# Motors_and_Servos.net
KiCad netlist of a schematic drawn in Altium Designer
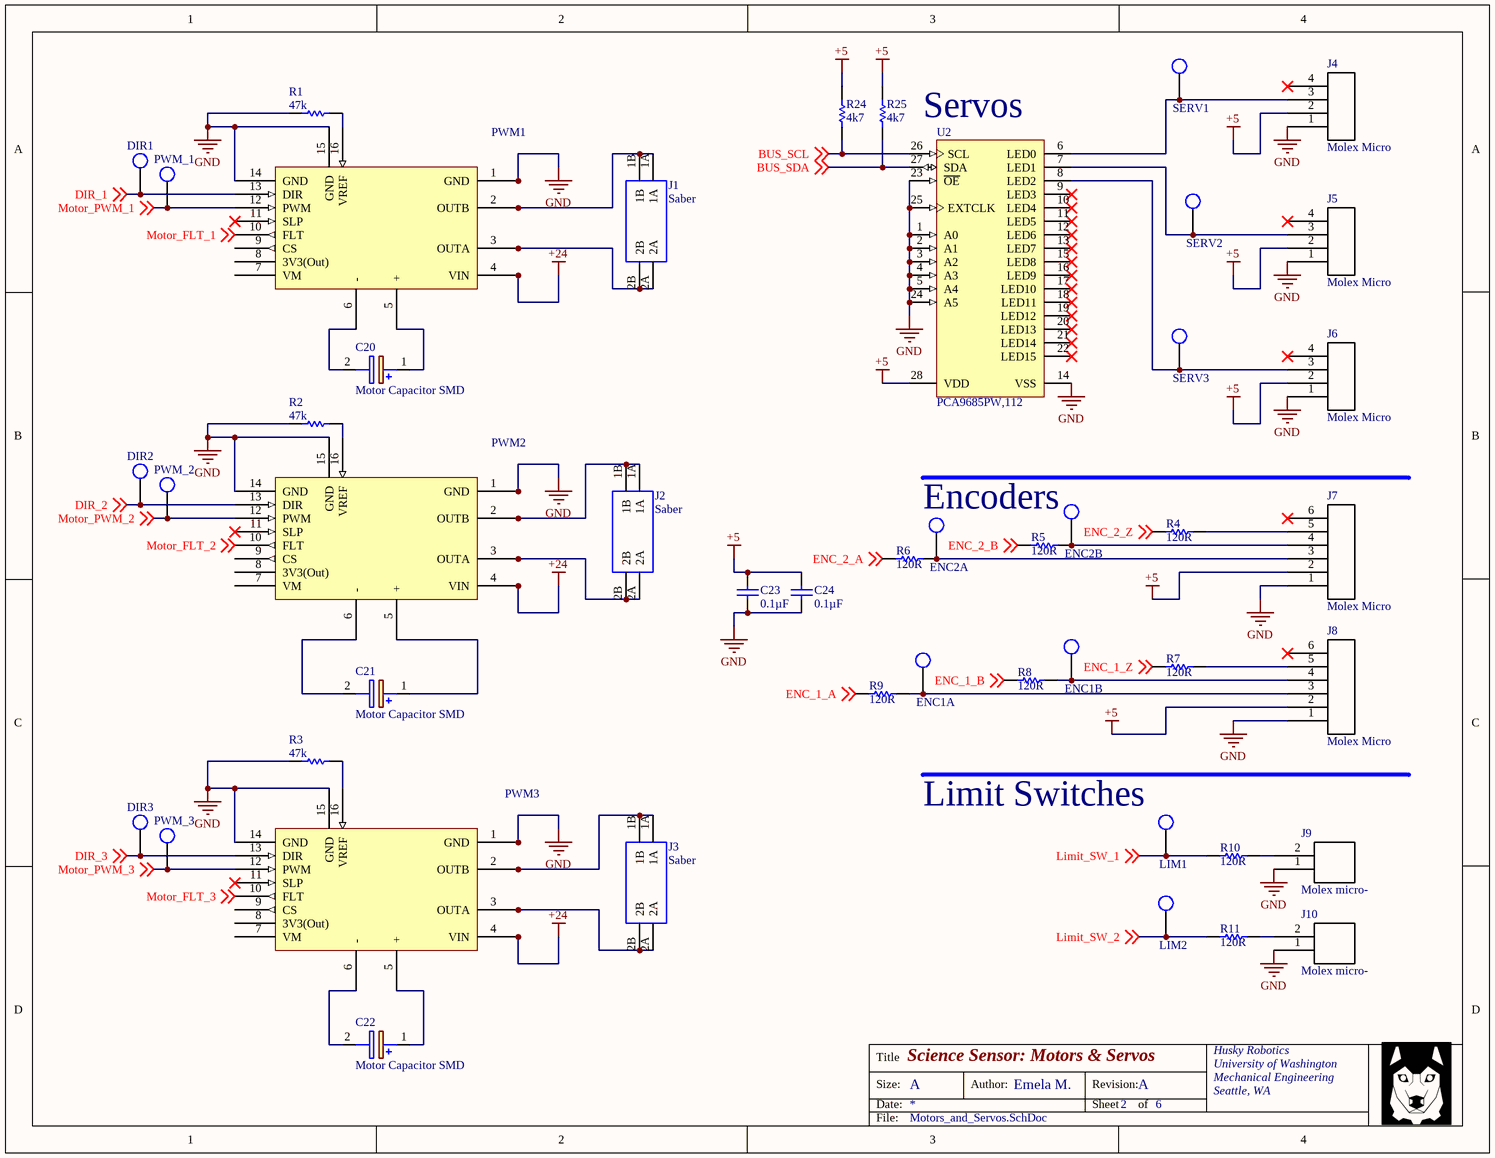
[diagram p0: Motors_and_Servos.SchDoc]

(export (version "E")
  (design (tool "Eeschema 10.0.6"))
  (components
    (comp (ref "C20")
      (value "Motor Capacitor SMD")
      (footprint "CAP_SMD_CAN")
      (description "Capacitor Polarised")
      (fields
        (field (name "MANUFACTURER_PART_NUMBER") "EEE-FK1V331AP")
        (field (name "MOUSER PART NUMBER") "667-EEE-FK1V331AP")
      )
      (libsource (lib "Husky Robotics Standard Library 2019-2020") (part "Motor Capacitor SMD"))
    )
    (comp (ref "C21")
      (value "Motor Capacitor SMD")
      (footprint "CAP_SMD_CAN")
      (description "Capacitor Polarised")
      (fields
        (field (name "MANUFACTURER_PART_NUMBER") "EEE-FK1V331AP")
        (field (name "MOUSER PART NUMBER") "667-EEE-FK1V331AP")
      )
      (libsource (lib "Husky Robotics Standard Library 2019-2020") (part "Motor Capacitor SMD"))
    )
    (comp (ref "C22")
      (value "Motor Capacitor SMD")
      (footprint "CAP_SMD_CAN")
      (description "Capacitor Polarised")
      (fields
        (field (name "MANUFACTURER_PART_NUMBER") "EEE-FK1V331AP")
        (field (name "MOUSER PART NUMBER") "667-EEE-FK1V331AP")
      )
      (libsource (lib "Husky Robotics Standard Library 2019-2020") (part "Motor Capacitor SMD"))
    )
    (comp (ref "C23")
      (value "Capacitor 0805")
      (footprint "Cap 0805")
      (description "Standard Capacitor")
      (fields (field (name "MANUFACTURER") "AVX") (field (name "CAPACITANCE") "0.1µF"))
      (libsource (lib "Standard Cap") (part "Capacitor 0805"))
    )
    (comp (ref "C24")
      (value "Capacitor 0805")
      (footprint "Cap 0805")
      (description "Standard Capacitor")
      (fields (field (name "MANUFACTURER") "AVX") (field (name "CAPACITANCE") "0.1µF"))
      (libsource (lib "Standard Cap") (part "Capacitor 0805"))
    )
    (comp (ref "DIR1")
      (value "Test Point")
      (footprint "Test Point Through-hole")
      (libsource (lib "Husky Robotics Standard Library 2019-2020") (part "Test Point"))
    )
    (comp (ref "DIR2")
      (value "Test Point")
      (footprint "Test Point Through-hole")
      (libsource (lib "Husky Robotics Standard Library 2019-2020") (part "Test Point"))
    )
    (comp (ref "DIR3")
      (value "Test Point")
      (footprint "Test Point Through-hole")
      (libsource (lib "Husky Robotics Standard Library 2019-2020") (part "Test Point"))
    )
    (comp (ref "ENC1A")
      (value "Test Point")
      (footprint "Test Point Through-hole")
      (libsource (lib "Husky Robotics Standard Library 2019-2020") (part "Test Point"))
    )
    (comp (ref "ENC1B")
      (value "Test Point")
      (footprint "Test Point Through-hole")
      (libsource (lib "Husky Robotics Standard Library 2019-2020") (part "Test Point"))
    )
    (comp (ref "ENC2A")
      (value "Test Point")
      (footprint "Test Point Through-hole")
      (libsource (lib "Husky Robotics Standard Library 2019-2020") (part "Test Point"))
    )
    (comp (ref "ENC2B")
      (value "Test Point")
      (footprint "Test Point Through-hole")
      (libsource (lib "Husky Robotics Standard Library 2019-2020") (part "Test Point"))
    )
    (comp (ref "J1")
      (value "Saber")
      (footprint "SABER R/A")
      (libsource (lib "Husky Robotics Standard Library 2019-2020") (part "Saber"))
    )
    (comp (ref "J2")
      (value "Saber")
      (footprint "SABER R/A")
      (libsource (lib "Husky Robotics Standard Library 2019-2020") (part "Saber"))
    )
    (comp (ref "J3")
      (value "Saber")
      (footprint "SABER R/A")
      (libsource (lib "Husky Robotics Standard Library 2019-2020") (part "Saber"))
    )
    (comp (ref "J4")
      (value "Molex Micro")
      (footprint "MICROFIT R/A 4 PIN")
      (description "Molex micro-fit 3.0 dual row header. P/N 0430450427")
      (libsource (lib "Husky Robotics Standard Library 2019-2020") (part "Molex micro-fit 4-pin (Single row schematic)"))
    )
    (comp (ref "J5")
      (value "Molex Micro")
      (footprint "MICROFIT R/A 4 PIN")
      (description "Molex micro-fit 3.0 dual row header. P/N 0430450427")
      (libsource (lib "Husky Robotics Standard Library 2019-2020") (part "Molex micro-fit 4-pin (Single row schematic)"))
    )
    (comp (ref "J6")
      (value "Molex Micro")
      (footprint "MICROFIT R/A 4 PIN")
      (description "Molex micro-fit 3.0 dual row header. P/N 0430450427")
      (libsource (lib "Husky Robotics Standard Library 2019-2020") (part "Molex micro-fit 4-pin (Single row schematic)"))
    )
    (comp (ref "J7")
      (value "Molex Micro")
      (footprint "MICROFIT R/A 6 PIN")
      (description "Molex micro-fit 3.0 dual row connector. P/N 0430450627")
      (libsource (lib "Husky Robotics Standard Library 2019-2020") (part "Molex micro-fit 6-pin (single row schematic)"))
    )
    (comp (ref "J8")
      (value "Molex Micro")
      (footprint "MICROFIT R/A 6 PIN")
      (description "Molex micro-fit 3.0 dual row connector. P/N 0430450627")
      (libsource (lib "Husky Robotics Standard Library 2019-2020") (part "Molex micro-fit 6-pin (single row schematic)"))
    )
    (comp (ref "J9")
      (value "Molex micro-")
      (footprint "microfit R/A 2 pin")
      (description "Molex micro-fit 3.0. Molex P/N 0430450227")
      (libsource (lib "Husky Robotics Standard Library 2019-2020") (part "Molex micro-fit 2-pin"))
    )
    (comp (ref "J10")
      (value "Molex micro-")
      (footprint "microfit R/A 2 pin")
      (description "Molex micro-fit 3.0. Molex P/N 0430450227")
      (libsource (lib "Husky Robotics Standard Library 2019-2020") (part "Molex micro-fit 2-pin"))
    )
    (comp (ref "LIM1")
      (value "Test Point")
      (footprint "Test Point Through-hole")
      (libsource (lib "Husky Robotics Standard Library 2019-2020") (part "Test Point"))
    )
    (comp (ref "LIM2")
      (value "Test Point")
      (footprint "Test Point Through-hole")
      (libsource (lib "Husky Robotics Standard Library 2019-2020") (part "Test Point"))
    )
    (comp (ref "PWM1")
      (value "6.5V - 40V")
      (footprint "Pololu_G2_Driver_24v21")
      (libsource (lib "Husky Robotics Standard Library 2019-2020") (part "Pololu G2 High-Power Motor Driver 24v21"))
    )
    (comp (ref "PWM2")
      (value "6.5V - 40V")
      (footprint "Pololu_G2_Driver_24v21")
      (libsource (lib "Husky Robotics Standard Library 2019-2020") (part "Pololu G2 High-Power Motor Driver 24v21"))
    )
    (comp (ref "PWM3")
      (value "6.5V - 40V")
      (footprint "Pololu_G2_Driver_24v21")
      (libsource (lib "Husky Robotics Standard Library 2019-2020") (part "Pololu G2 High-Power Motor Driver 24v21"))
    )
    (comp (ref "PWM_1")
      (value "Test Point")
      (footprint "Test Point Through-hole")
      (libsource (lib "Husky Robotics Standard Library 2019-2020") (part "Test Point"))
    )
    (comp (ref "PWM_2")
      (value "Test Point")
      (footprint "Test Point Through-hole")
      (libsource (lib "Husky Robotics Standard Library 2019-2020") (part "Test Point"))
    )
    (comp (ref "PWM_3")
      (value "Test Point")
      (footprint "Test Point Through-hole")
      (libsource (lib "Husky Robotics Standard Library 2019-2020") (part "Test Point"))
    )
    (comp (ref "R1")
      (value "47k")
      (footprint "RESC0805(2012)_N")
      (description "Generic 0805 Resistor")
      (fields (field (name "TOLERANCE") "5 %") (field (name "POWER") "0.125 W"))
      (libsource (lib "Husky Robotics Standard Library 2019-2020") (part "Resistor 0805"))
    )
    (comp (ref "R2")
      (value "47k")
      (footprint "RESC0805(2012)_N")
      (description "Generic 0805 Resistor")
      (fields (field (name "TOLERANCE") "5 %") (field (name "POWER") "0.125 W"))
      (libsource (lib "Husky Robotics Standard Library 2019-2020") (part "Resistor 0805"))
    )
    (comp (ref "R3")
      (value "47k")
      (footprint "RESC0805(2012)_N")
      (description "Generic 0805 Resistor")
      (fields (field (name "TOLERANCE") "5 %") (field (name "POWER") "0.125 W"))
      (libsource (lib "Husky Robotics Standard Library 2019-2020") (part "Resistor 0805"))
    )
    (comp (ref "R4")
      (value "120R")
      (footprint "RESC0805(2012)_N")
      (description "Generic 0805 Resistor")
      (fields (field (name "TOLERANCE") "5 %") (field (name "POWER") "0.125 W"))
      (libsource (lib "Husky Robotics Standard Library 2019-2020") (part "Resistor 0805"))
    )
    (comp (ref "R5")
      (value "120R")
      (footprint "RESC0805(2012)_N")
      (description "Generic 0805 Resistor")
      (fields (field (name "TOLERANCE") "5 %") (field (name "POWER") "0.125 W"))
      (libsource (lib "Husky Robotics Standard Library 2019-2020") (part "Resistor 0805"))
    )
    (comp (ref "R6")
      (value "120R")
      (footprint "RESC0805(2012)_N")
      (description "Generic 0805 Resistor")
      (fields (field (name "TOLERANCE") "5 %") (field (name "POWER") "0.125 W"))
      (libsource (lib "Husky Robotics Standard Library 2019-2020") (part "Resistor 0805"))
    )
    (comp (ref "R7")
      (value "120R")
      (footprint "RESC0805(2012)_N")
      (description "Generic 0805 Resistor")
      (fields (field (name "TOLERANCE") "5 %") (field (name "POWER") "0.125 W"))
      (libsource (lib "Husky Robotics Standard Library 2019-2020") (part "Resistor 0805"))
    )
    (comp (ref "R8")
      (value "120R")
      (footprint "RESC0805(2012)_N")
      (description "Generic 0805 Resistor")
      (fields (field (name "TOLERANCE") "5 %") (field (name "POWER") "0.125 W"))
      (libsource (lib "Husky Robotics Standard Library 2019-2020") (part "Resistor 0805"))
    )
    (comp (ref "R9")
      (value "120R")
      (footprint "RESC0805(2012)_N")
      (description "Generic 0805 Resistor")
      (fields (field (name "TOLERANCE") "5 %") (field (name "POWER") "0.125 W"))
      (libsource (lib "Husky Robotics Standard Library 2019-2020") (part "Resistor 0805"))
    )
    (comp (ref "R10")
      (value "120R")
      (footprint "RESC0805(2012)_N")
      (description "Generic 0805 Resistor")
      (fields (field (name "TOLERANCE") "5 %") (field (name "POWER") "0.125 W"))
      (libsource (lib "Husky Robotics Standard Library 2019-2020") (part "Resistor 0805"))
    )
    (comp (ref "R11")
      (value "120R")
      (footprint "RESC0805(2012)_N")
      (description "Generic 0805 Resistor")
      (fields (field (name "TOLERANCE") "5 %") (field (name "POWER") "0.125 W"))
      (libsource (lib "Husky Robotics Standard Library 2019-2020") (part "Resistor 0805"))
    )
    (comp (ref "R24")
      (value "4k7")
      (footprint "RESC0805(2012)_N")
      (description "Generic 0805 Resistor")
      (fields (field (name "TOLERANCE") "5 %") (field (name "POWER") "0.125 W"))
      (libsource (lib "Husky Robotics Standard Library 2019-2020") (part "Resistor 0805"))
    )
    (comp (ref "R25")
      (value "4k7")
      (footprint "RESC0805(2012)_N")
      (description "Generic 0805 Resistor")
      (fields (field (name "TOLERANCE") "5 %") (field (name "POWER") "0.125 W"))
      (libsource (lib "Husky Robotics Standard Library 2019-2020") (part "Resistor 0805"))
    )
    (comp (ref "SERV1")
      (value "Test Point")
      (footprint "Test Point Through-hole")
      (libsource (lib "Husky Robotics Standard Library 2019-2020") (part "Test Point"))
    )
    (comp (ref "SERV2")
      (value "Test Point")
      (footprint "Test Point Through-hole")
      (libsource (lib "Husky Robotics Standard Library 2019-2020") (part "Test Point"))
    )
    (comp (ref "SERV3")
      (value "Test Point")
      (footprint "Test Point Through-hole")
      (libsource (lib "Husky Robotics Standard Library 2019-2020") (part "Test Point"))
    )
    (comp (ref "U2")
      (value "PCA9685PW,112")
      (footprint "SOT361-1_V")
      (fields (field (name "PARTNUMBER") "PCA9685"))
      (libsource (lib "Altium Content Vault") (part "NXP-PCA9685-SOT361-1"))
    )
  )
  (nets
    (net (code "1") (name "+5") (class "Default")
      (node (ref "C23") (pin "2") (pinfunction "2_2") (pintype "passive"))
      (node (ref "C24") (pin "2") (pinfunction "2_2") (pintype "passive"))
      (node (ref "J4") (pin "2") (pintype "passive"))
      (node (ref "J5") (pin "2") (pintype "passive"))
      (node (ref "J6") (pin "2") (pintype "passive"))
      (node (ref "J7") (pin "2") (pintype "passive"))
      (node (ref "J8") (pin "2") (pintype "passive"))
      (node (ref "R24") (pin "2") (pinfunction "2_2") (pintype "passive"))
      (node (ref "R25") (pin "2") (pinfunction "2_2") (pintype "passive"))
      (node (ref "U2") (pin "28") (pinfunction "VDD_28") (pintype "power_in"))
    )
    (net (code "2") (name "+24") (class "Default")
      (node (ref "PWM1") (pin "4") (pinfunction "VIN_4") (pintype "power_in"))
      (node (ref "PWM1") (pin "4a") (pinfunction "VIN_4a") (pintype "passive"))
      (node (ref "PWM1") (pin "4b") (pinfunction "VIN_4b") (pintype "passive"))
      (node (ref "PWM2") (pin "4") (pinfunction "VIN_4") (pintype "power_in"))
      (node (ref "PWM2") (pin "4a") (pinfunction "VIN_4a") (pintype "passive"))
      (node (ref "PWM2") (pin "4b") (pinfunction "VIN_4b") (pintype "passive"))
      (node (ref "PWM3") (pin "4") (pinfunction "VIN_4") (pintype "power_in"))
      (node (ref "PWM3") (pin "4a") (pinfunction "VIN_4a") (pintype "passive"))
      (node (ref "PWM3") (pin "4b") (pinfunction "VIN_4b") (pintype "passive"))
    )
    (net (code "3") (name "BUS_SCL") (class "Default")
      (node (ref "R24") (pin "1") (pinfunction "1_1") (pintype "passive"))
      (node (ref "U2") (pin "26") (pinfunction "SCL_26") (pintype "input"))
    )
    (net (code "4") (name "BUS_SDA") (class "Default")
      (node (ref "R25") (pin "1") (pinfunction "1_1") (pintype "passive"))
      (node (ref "U2") (pin "27") (pinfunction "SDA_27") (pintype "bidirectional"))
    )
    (net (code "5") (name "DIR_1") (class "Default")
      (node (ref "DIR1") (pin "1") (pinfunction "1_1") (pintype "passive"))
      (node (ref "PWM1") (pin "13") (pinfunction "DIR_13") (pintype "input"))
    )
    (net (code "6") (name "DIR_2") (class "Default")
      (node (ref "DIR2") (pin "1") (pinfunction "1_1") (pintype "passive"))
      (node (ref "PWM2") (pin "13") (pinfunction "DIR_13") (pintype "input"))
    )
    (net (code "7") (name "DIR_3") (class "Default")
      (node (ref "DIR3") (pin "1") (pinfunction "1_1") (pintype "passive"))
      (node (ref "PWM3") (pin "13") (pinfunction "DIR_13") (pintype "input"))
    )
    (net (code "8") (name "ENC_1_A") (class "Default")
      (node (ref "R9") (pin "1") (pinfunction "1_1") (pintype "passive"))
    )
    (net (code "9") (name "ENC_1_B") (class "Default")
      (node (ref "R8") (pin "1") (pinfunction "1_1") (pintype "passive"))
    )
    (net (code "10") (name "ENC_1_Z") (class "Default")
      (node (ref "R7") (pin "1") (pinfunction "1_1") (pintype "passive"))
    )
    (net (code "11") (name "ENC_2_A") (class "Default")
      (node (ref "R6") (pin "1") (pinfunction "1_1") (pintype "passive"))
    )
    (net (code "12") (name "ENC_2_B") (class "Default")
      (node (ref "R5") (pin "1") (pinfunction "1_1") (pintype "passive"))
    )
    (net (code "13") (name "ENC_2_Z") (class "Default")
      (node (ref "R4") (pin "1") (pinfunction "1_1") (pintype "passive"))
    )
    (net (code "14") (name "GND") (class "Default")
      (node (ref "C23") (pin "1") (pinfunction "1_1") (pintype "passive"))
      (node (ref "C24") (pin "1") (pinfunction "1_1") (pintype "passive"))
      (node (ref "J10") (pin "1") (pintype "passive"))
      (node (ref "J4") (pin "1") (pintype "passive"))
      (node (ref "J5") (pin "1") (pintype "passive"))
      (node (ref "J6") (pin "1") (pintype "passive"))
      (node (ref "J7") (pin "1") (pintype "passive"))
      (node (ref "J8") (pin "1") (pintype "passive"))
      (node (ref "J9") (pin "1") (pintype "passive"))
      (node (ref "PWM1") (pin "1") (pinfunction "GND_1") (pintype "power_in"))
      (node (ref "PWM1") (pin "14") (pinfunction "GND_14") (pintype "power_in"))
      (node (ref "PWM1") (pin "15") (pinfunction "GND_15") (pintype "power_in"))
      (node (ref "PWM1") (pin "1a") (pinfunction "GND_1a") (pintype "passive"))
      (node (ref "PWM1") (pin "1b") (pinfunction "GND_1b") (pintype "passive"))
      (node (ref "PWM2") (pin "1") (pinfunction "GND_1") (pintype "power_in"))
      (node (ref "PWM2") (pin "14") (pinfunction "GND_14") (pintype "power_in"))
      (node (ref "PWM2") (pin "15") (pinfunction "GND_15") (pintype "power_in"))
      (node (ref "PWM2") (pin "1a") (pinfunction "GND_1a") (pintype "passive"))
      (node (ref "PWM2") (pin "1b") (pinfunction "GND_1b") (pintype "passive"))
      (node (ref "PWM3") (pin "1") (pinfunction "GND_1") (pintype "power_in"))
      (node (ref "PWM3") (pin "14") (pinfunction "GND_14") (pintype "power_in"))
      (node (ref "PWM3") (pin "15") (pinfunction "GND_15") (pintype "power_in"))
      (node (ref "PWM3") (pin "1a") (pinfunction "GND_1a") (pintype "passive"))
      (node (ref "PWM3") (pin "1b") (pinfunction "GND_1b") (pintype "passive"))
      (node (ref "R1") (pin "2") (pinfunction "2_2") (pintype "passive"))
      (node (ref "R2") (pin "2") (pinfunction "2_2") (pintype "passive"))
      (node (ref "R3") (pin "2") (pinfunction "2_2") (pintype "passive"))
      (node (ref "U2") (pin "1") (pinfunction "A0_1") (pintype "input"))
      (node (ref "U2") (pin "14") (pinfunction "VSS_14") (pintype "power_in"))
      (node (ref "U2") (pin "2") (pinfunction "A1_2") (pintype "input"))
      (node (ref "U2") (pin "23") (pinfunction "~{OE}_23") (pintype "input"))
      (node (ref "U2") (pin "24") (pinfunction "A5_24") (pintype "input"))
      (node (ref "U2") (pin "25") (pinfunction "EXTCLK_25") (pintype "input"))
      (node (ref "U2") (pin "3") (pinfunction "A2_3") (pintype "input"))
      (node (ref "U2") (pin "4") (pinfunction "A3_4") (pintype "input"))
      (node (ref "U2") (pin "5") (pinfunction "A4_5") (pintype "input"))
    )
    (net (code "15") (name "Limit_SW_1") (class "Default")
      (node (ref "LIM1") (pin "1") (pinfunction "1_1") (pintype "passive"))
      (node (ref "R10") (pin "1") (pinfunction "1_1") (pintype "passive"))
    )
    (net (code "16") (name "Limit_SW_2") (class "Default")
      (node (ref "LIM2") (pin "1") (pinfunction "1_1") (pintype "passive"))
      (node (ref "R11") (pin "1") (pinfunction "1_1") (pintype "passive"))
    )
    (net (code "17") (name "Motor_FLT_1") (class "Default")
      (node (ref "PWM1") (pin "10") (pinfunction "FLT_10") (pintype "output"))
    )
    (net (code "18") (name "Motor_FLT_2") (class "Default")
      (node (ref "PWM2") (pin "10") (pinfunction "FLT_10") (pintype "output"))
    )
    (net (code "19") (name "Motor_FLT_3") (class "Default")
      (node (ref "PWM3") (pin "10") (pinfunction "FLT_10") (pintype "output"))
    )
    (net (code "20") (name "Motor_PWM_1") (class "Default")
      (node (ref "PWM1") (pin "12") (pinfunction "PWM_12") (pintype "input"))
      (node (ref "PWM_1") (pin "1") (pinfunction "1_1") (pintype "passive"))
    )
    (net (code "21") (name "Motor_PWM_2") (class "Default")
      (node (ref "PWM2") (pin "12") (pinfunction "PWM_12") (pintype "input"))
      (node (ref "PWM_2") (pin "1") (pinfunction "1_1") (pintype "passive"))
    )
    (net (code "22") (name "Motor_PWM_3") (class "Default")
      (node (ref "PWM3") (pin "12") (pinfunction "PWM_12") (pintype "input"))
      (node (ref "PWM_3") (pin "1") (pinfunction "1_1") (pintype "passive"))
    )
    (net (code "23") (name "Net-(C20-+)") (class "Default")
      (node (ref "C20") (pin "1") (pinfunction "+_1") (pintype "passive"))
      (node (ref "PWM1") (pin "5") (pinfunction "+_5") (pintype "power_in"))
    )
    (net (code "24") (name "Net-(C20--)") (class "Default")
      (node (ref "C20") (pin "2") (pinfunction "-_2") (pintype "passive"))
      (node (ref "PWM1") (pin "6") (pinfunction "-_6") (pintype "power_in"))
    )
    (net (code "25") (name "Net-(C21-+)") (class "Default")
      (node (ref "C21") (pin "1") (pinfunction "+_1") (pintype "passive"))
      (node (ref "PWM2") (pin "5") (pinfunction "+_5") (pintype "power_in"))
    )
    (net (code "26") (name "Net-(C21--)") (class "Default")
      (node (ref "C21") (pin "2") (pinfunction "-_2") (pintype "passive"))
      (node (ref "PWM2") (pin "6") (pinfunction "-_6") (pintype "power_in"))
    )
    (net (code "27") (name "Net-(C22-+)") (class "Default")
      (node (ref "C22") (pin "1") (pinfunction "+_1") (pintype "passive"))
      (node (ref "PWM3") (pin "5") (pinfunction "+_5") (pintype "power_in"))
    )
    (net (code "28") (name "Net-(C22--)") (class "Default")
      (node (ref "C22") (pin "2") (pinfunction "-_2") (pintype "passive"))
      (node (ref "PWM3") (pin "6") (pinfunction "-_6") (pintype "power_in"))
    )
    (net (code "29") (name "Net-(ENC1A-Pad1)") (class "Default")
      (node (ref "ENC1A") (pin "1") (pinfunction "1_1") (pintype "passive"))
      (node (ref "J8") (pin "3") (pintype "passive"))
      (node (ref "R9") (pin "2") (pinfunction "2_2") (pintype "passive"))
    )
    (net (code "30") (name "Net-(ENC1B-Pad1)") (class "Default")
      (node (ref "ENC1B") (pin "1") (pinfunction "1_1") (pintype "passive"))
      (node (ref "J8") (pin "4") (pintype "passive"))
      (node (ref "R8") (pin "2") (pinfunction "2_2") (pintype "passive"))
    )
    (net (code "31") (name "Net-(ENC2A-Pad1)") (class "Default")
      (node (ref "ENC2A") (pin "1") (pinfunction "1_1") (pintype "passive"))
      (node (ref "J7") (pin "3") (pintype "passive"))
      (node (ref "R6") (pin "2") (pinfunction "2_2") (pintype "passive"))
    )
    (net (code "32") (name "Net-(ENC2B-Pad1)") (class "Default")
      (node (ref "ENC2B") (pin "1") (pinfunction "1_1") (pintype "passive"))
      (node (ref "J7") (pin "4") (pintype "passive"))
      (node (ref "R5") (pin "2") (pinfunction "2_2") (pintype "passive"))
    )
    (net (code "33") (name "Net-(J1-Pad1A)") (class "Default")
      (node (ref "J1") (pin "1A") (pinfunction "1A_1A") (pintype "passive"))
      (node (ref "J1") (pin "1B") (pinfunction "1B_1B") (pintype "passive"))
      (node (ref "PWM1") (pin "2") (pinfunction "OUTB_2") (pintype "power_in"))
      (node (ref "PWM1") (pin "2a") (pinfunction "OUTB_2a") (pintype "passive"))
      (node (ref "PWM1") (pin "2b") (pinfunction "OUTB_2b") (pintype "passive"))
    )
    (net (code "34") (name "Net-(J1-Pad2A)") (class "Default")
      (node (ref "J1") (pin "2A") (pinfunction "2A_2A") (pintype "passive"))
      (node (ref "J1") (pin "2B") (pinfunction "2B_2B") (pintype "passive"))
      (node (ref "PWM1") (pin "3") (pinfunction "OUTA_3") (pintype "passive"))
      (node (ref "PWM1") (pin "3a") (pinfunction "OUTA_3a") (pintype "passive"))
      (node (ref "PWM1") (pin "3b") (pinfunction "OUTA_3b") (pintype "power_in"))
    )
    (net (code "35") (name "Net-(J2-Pad1A)") (class "Default")
      (node (ref "J2") (pin "1A") (pinfunction "1A_1A") (pintype "passive"))
      (node (ref "J2") (pin "1B") (pinfunction "1B_1B") (pintype "passive"))
      (node (ref "PWM2") (pin "2") (pinfunction "OUTB_2") (pintype "power_in"))
      (node (ref "PWM2") (pin "2a") (pinfunction "OUTB_2a") (pintype "passive"))
      (node (ref "PWM2") (pin "2b") (pinfunction "OUTB_2b") (pintype "passive"))
    )
    (net (code "36") (name "Net-(J2-Pad2A)") (class "Default")
      (node (ref "J2") (pin "2A") (pinfunction "2A_2A") (pintype "passive"))
      (node (ref "J2") (pin "2B") (pinfunction "2B_2B") (pintype "passive"))
      (node (ref "PWM2") (pin "3") (pinfunction "OUTA_3") (pintype "passive"))
      (node (ref "PWM2") (pin "3a") (pinfunction "OUTA_3a") (pintype "passive"))
      (node (ref "PWM2") (pin "3b") (pinfunction "OUTA_3b") (pintype "power_in"))
    )
    (net (code "37") (name "Net-(J3-Pad1A)") (class "Default")
      (node (ref "J3") (pin "1A") (pinfunction "1A_1A") (pintype "passive"))
      (node (ref "J3") (pin "1B") (pinfunction "1B_1B") (pintype "passive"))
      (node (ref "PWM3") (pin "2") (pinfunction "OUTB_2") (pintype "power_in"))
      (node (ref "PWM3") (pin "2a") (pinfunction "OUTB_2a") (pintype "passive"))
      (node (ref "PWM3") (pin "2b") (pinfunction "OUTB_2b") (pintype "passive"))
    )
    (net (code "38") (name "Net-(J3-Pad2A)") (class "Default")
      (node (ref "J3") (pin "2A") (pinfunction "2A_2A") (pintype "passive"))
      (node (ref "J3") (pin "2B") (pinfunction "2B_2B") (pintype "passive"))
      (node (ref "PWM3") (pin "3") (pinfunction "OUTA_3") (pintype "passive"))
      (node (ref "PWM3") (pin "3a") (pinfunction "OUTA_3a") (pintype "passive"))
      (node (ref "PWM3") (pin "3b") (pinfunction "OUTA_3b") (pintype "power_in"))
    )
    (net (code "39") (name "Net-(J7-Pad5)") (class "Default")
      (node (ref "J7") (pin "5") (pintype "passive"))
      (node (ref "R4") (pin "2") (pinfunction "2_2") (pintype "passive"))
    )
    (net (code "40") (name "Net-(J8-Pad5)") (class "Default")
      (node (ref "J8") (pin "5") (pintype "passive"))
      (node (ref "R7") (pin "2") (pinfunction "2_2") (pintype "passive"))
    )
    (net (code "41") (name "Net-(J9-Pad2)") (class "Default")
      (node (ref "J9") (pin "2") (pintype "passive"))
      (node (ref "R10") (pin "2") (pinfunction "2_2") (pintype "passive"))
    )
    (net (code "42") (name "Net-(J10-Pad2)") (class "Default")
      (node (ref "J10") (pin "2") (pintype "passive"))
      (node (ref "R11") (pin "2") (pinfunction "2_2") (pintype "passive"))
    )
    (net (code "43") (name "Net-(PWM1-VREF)") (class "Default")
      (node (ref "PWM1") (pin "16") (pinfunction "VREF_16") (pintype "input"))
      (node (ref "R1") (pin "1") (pinfunction "1_1") (pintype "passive"))
    )
    (net (code "44") (name "Net-(PWM2-VREF)") (class "Default")
      (node (ref "PWM2") (pin "16") (pinfunction "VREF_16") (pintype "input"))
      (node (ref "R2") (pin "1") (pinfunction "1_1") (pintype "passive"))
    )
    (net (code "45") (name "Net-(PWM3-VREF)") (class "Default")
      (node (ref "PWM3") (pin "16") (pinfunction "VREF_16") (pintype "input"))
      (node (ref "R3") (pin "1") (pinfunction "1_1") (pintype "passive"))
    )
    (net (code "46") (name "Net-(U2-LED0)") (class "Default")
      (node (ref "J4") (pin "3") (pintype "passive"))
      (node (ref "SERV1") (pin "1") (pinfunction "1_1") (pintype "passive"))
      (node (ref "U2") (pin "6") (pinfunction "LED0_6") (pintype "tri_state"))
    )
    (net (code "47") (name "Net-(U2-LED1)") (class "Default")
      (node (ref "J5") (pin "3") (pintype "passive"))
      (node (ref "SERV2") (pin "1") (pinfunction "1_1") (pintype "passive"))
      (node (ref "U2") (pin "7") (pinfunction "LED1_7") (pintype "tri_state"))
    )
    (net (code "48") (name "Net-(U2-LED2)") (class "Default")
      (node (ref "J6") (pin "3") (pintype "passive"))
      (node (ref "SERV3") (pin "1") (pinfunction "1_1") (pintype "passive"))
      (node (ref "U2") (pin "8") (pinfunction "LED2_8") (pintype "tri_state"))
    )
    (net (code "49") (name "unconnected-(J4-Pad4)") (class "Default")
      (node (ref "J4") (pin "4") (pintype "passive+no_connect"))
    )
    (net (code "50") (name "unconnected-(J5-Pad4)") (class "Default")
      (node (ref "J5") (pin "4") (pintype "passive+no_connect"))
    )
    (net (code "51") (name "unconnected-(J6-Pad4)") (class "Default")
      (node (ref "J6") (pin "4") (pintype "passive+no_connect"))
    )
    (net (code "52") (name "unconnected-(J7-Pad6)") (class "Default")
      (node (ref "J7") (pin "6") (pintype "passive+no_connect"))
    )
    (net (code "53") (name "unconnected-(J8-Pad6)") (class "Default")
      (node (ref "J8") (pin "6") (pintype "passive+no_connect"))
    )
    (net (code "54") (name "unconnected-(PWM1-3V3(Out)-Pad8)") (class "Default")
      (node (ref "PWM1") (pin "8") (pinfunction "3V3(Out)_8") (pintype "power_in"))
    )
    (net (code "55") (name "unconnected-(PWM1-CS-Pad9)") (class "Default")
      (node (ref "PWM1") (pin "9") (pinfunction "CS_9") (pintype "output"))
    )
    (net (code "56") (name "unconnected-(PWM1-SLP-Pad11)") (class "Default")
      (node (ref "PWM1") (pin "11") (pinfunction "SLP_11") (pintype "input+no_connect"))
    )
    (net (code "57") (name "unconnected-(PWM1-VM-Pad7)") (class "Default")
      (node (ref "PWM1") (pin "7") (pinfunction "VM_7") (pintype "power_in"))
    )
    (net (code "58") (name "unconnected-(PWM2-3V3(Out)-Pad8)") (class "Default")
      (node (ref "PWM2") (pin "8") (pinfunction "3V3(Out)_8") (pintype "power_in"))
    )
    (net (code "59") (name "unconnected-(PWM2-CS-Pad9)") (class "Default")
      (node (ref "PWM2") (pin "9") (pinfunction "CS_9") (pintype "output"))
    )
    (net (code "60") (name "unconnected-(PWM2-SLP-Pad11)") (class "Default")
      (node (ref "PWM2") (pin "11") (pinfunction "SLP_11") (pintype "input+no_connect"))
    )
    (net (code "61") (name "unconnected-(PWM2-VM-Pad7)") (class "Default")
      (node (ref "PWM2") (pin "7") (pinfunction "VM_7") (pintype "power_in"))
    )
    (net (code "62") (name "unconnected-(PWM3-3V3(Out)-Pad8)") (class "Default")
      (node (ref "PWM3") (pin "8") (pinfunction "3V3(Out)_8") (pintype "power_in"))
    )
    (net (code "63") (name "unconnected-(PWM3-CS-Pad9)") (class "Default")
      (node (ref "PWM3") (pin "9") (pinfunction "CS_9") (pintype "output"))
    )
    (net (code "64") (name "unconnected-(PWM3-SLP-Pad11)") (class "Default")
      (node (ref "PWM3") (pin "11") (pinfunction "SLP_11") (pintype "input+no_connect"))
    )
    (net (code "65") (name "unconnected-(PWM3-VM-Pad7)") (class "Default")
      (node (ref "PWM3") (pin "7") (pinfunction "VM_7") (pintype "power_in"))
    )
    (net (code "66") (name "unconnected-(U2-LED3-Pad9)") (class "Default")
      (node (ref "U2") (pin "9") (pinfunction "LED3_9") (pintype "tri_state+no_connect"))
    )
    (net (code "67") (name "unconnected-(U2-LED4-Pad10)") (class "Default")
      (node (ref "U2") (pin "10") (pinfunction "LED4_10") (pintype "tri_state+no_connect"))
    )
    (net (code "68") (name "unconnected-(U2-LED5-Pad11)") (class "Default")
      (node (ref "U2") (pin "11") (pinfunction "LED5_11") (pintype "tri_state+no_connect"))
    )
    (net (code "69") (name "unconnected-(U2-LED6-Pad12)") (class "Default")
      (node (ref "U2") (pin "12") (pinfunction "LED6_12") (pintype "tri_state+no_connect"))
    )
    (net (code "70") (name "unconnected-(U2-LED7-Pad13)") (class "Default")
      (node (ref "U2") (pin "13") (pinfunction "LED7_13") (pintype "tri_state+no_connect"))
    )
    (net (code "71") (name "unconnected-(U2-LED8-Pad15)") (class "Default")
      (node (ref "U2") (pin "15") (pinfunction "LED8_15") (pintype "tri_state+no_connect"))
    )
    (net (code "72") (name "unconnected-(U2-LED9-Pad16)") (class "Default")
      (node (ref "U2") (pin "16") (pinfunction "LED9_16") (pintype "tri_state+no_connect"))
    )
    (net (code "73") (name "unconnected-(U2-LED10-Pad17)") (class "Default")
      (node (ref "U2") (pin "17") (pinfunction "LED10_17") (pintype "tri_state+no_connect"))
    )
    (net (code "74") (name "unconnected-(U2-LED11-Pad18)") (class "Default")
      (node (ref "U2") (pin "18") (pinfunction "LED11_18") (pintype "tri_state+no_connect"))
    )
    (net (code "75") (name "unconnected-(U2-LED12-Pad19)") (class "Default")
      (node (ref "U2") (pin "19") (pinfunction "LED12_19") (pintype "tri_state+no_connect"))
    )
    (net (code "76") (name "unconnected-(U2-LED13-Pad20)") (class "Default")
      (node (ref "U2") (pin "20") (pinfunction "LED13_20") (pintype "tri_state+no_connect"))
    )
    (net (code "77") (name "unconnected-(U2-LED14-Pad21)") (class "Default")
      (node (ref "U2") (pin "21") (pinfunction "LED14_21") (pintype "tri_state+no_connect"))
    )
    (net (code "78") (name "unconnected-(U2-LED15-Pad22)") (class "Default")
      (node (ref "U2") (pin "22") (pinfunction "LED15_22") (pintype "tri_state+no_connect"))
    )
  )
)
